# ADE7753.net
KiCad netlist of a schematic drawn in Altium Designer
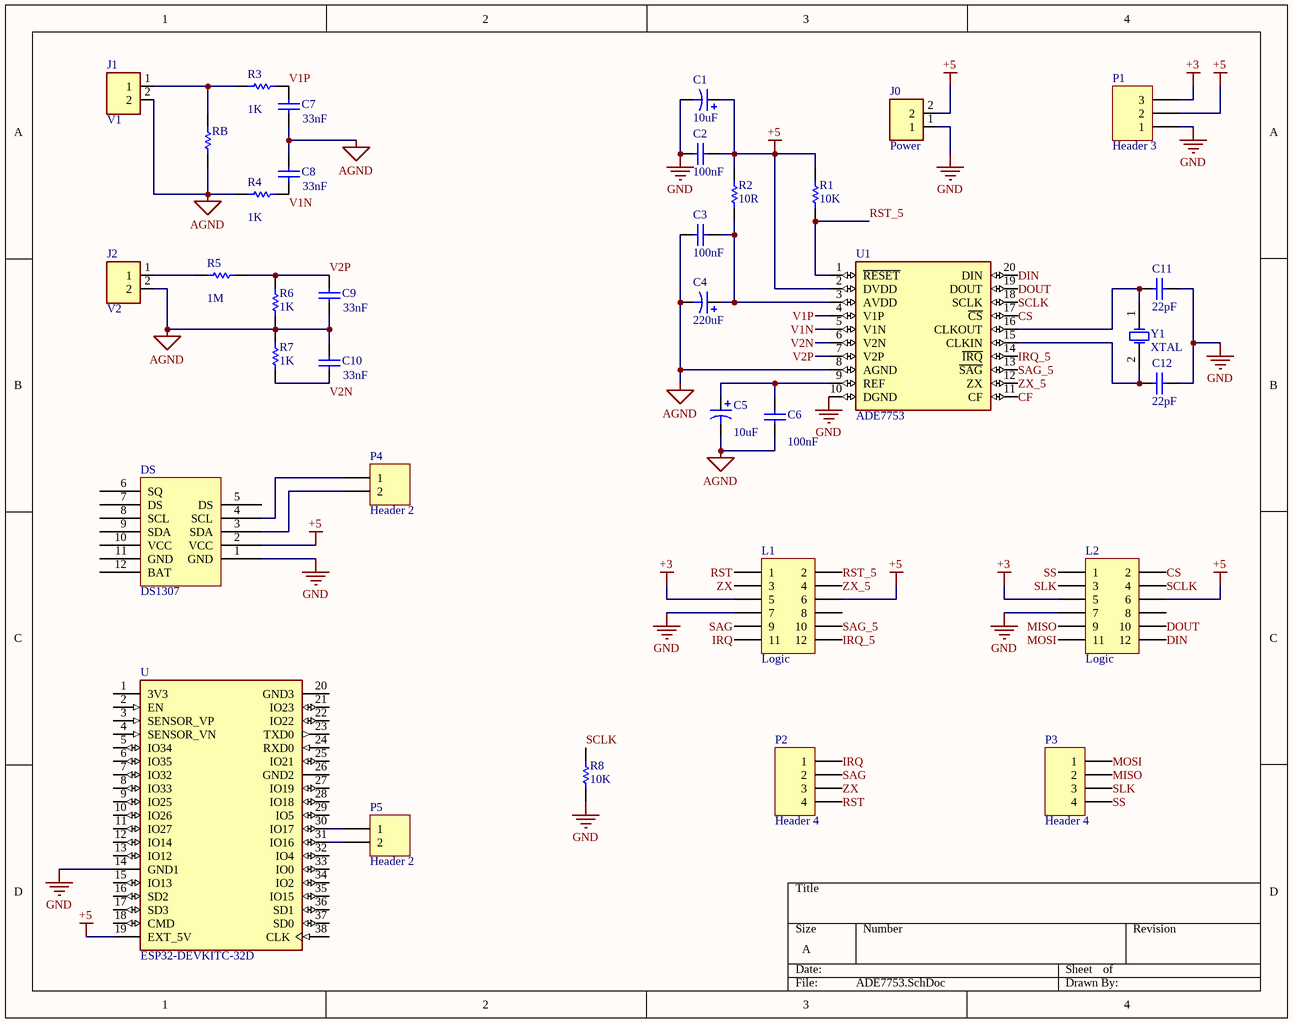
[diagram p0: ADE7753.SchDoc]

(export (version "E")
  (design (tool "Eeschema 10.0.6"))
  (components
    (comp (ref "C1")
      (value "10uF")
      (footprint "Tu hóa 10uF 50v")
      (description "Polarized Capacitor (Radial)")
      (fields (field (name "Comment") "Cap Pol1") (field (name "PUBLISHER") "Altium Limited"))
      (libsource (lib "Miscellaneous Devices") (part "Cap Pol1"))
    )
    (comp (ref "C2")
      (value "100nF")
      (footprint "Tu Gom")
      (description "Capacitor")
      (fields (field (name "Comment") "Cap") (field (name "PUBLISHER") "Altium Limited"))
      (libsource (lib "Miscellaneous Devices") (part "Cap"))
    )
    (comp (ref "C3")
      (value "100nF")
      (footprint "Tu Gom")
      (description "Capacitor")
      (fields (field (name "Comment") "Cap") (field (name "PUBLISHER") "Altium Limited"))
      (libsource (lib "Miscellaneous Devices") (part "Cap"))
    )
    (comp (ref "C4")
      (value "220uF")
      (footprint "Tu hóa 10uF 50v")
      (description "Polarized Capacitor (Radial)")
      (fields (field (name "Comment") "Cap Pol1") (field (name "PUBLISHER") "Altium Limited"))
      (libsource (lib "Miscellaneous Devices") (part "Cap Pol1"))
    )
    (comp (ref "C5")
      (value "10uF")
      (footprint "Tu hóa 10uF 50v")
      (description "Polarized Capacitor (Radial)")
      (fields (field (name "Comment") "Cap Pol1") (field (name "PUBLISHER") "Altium Limited"))
      (libsource (lib "Miscellaneous Devices") (part "Cap Pol1"))
    )
    (comp (ref "C6")
      (value "100nF")
      (footprint "Tu Gom")
      (description "Capacitor")
      (fields (field (name "Comment") "Cap") (field (name "PUBLISHER") "Altium Limited"))
      (libsource (lib "Miscellaneous Devices") (part "Cap"))
    )
    (comp (ref "C7")
      (value "33nF")
      (footprint "Tu Gom")
      (description "Capacitor")
      (fields (field (name "Comment") "Cap") (field (name "PUBLISHER") "Altium Limited"))
      (libsource (lib "Miscellaneous Devices") (part "Cap"))
    )
    (comp (ref "C8")
      (value "33nF")
      (footprint "Tu Gom")
      (description "Capacitor")
      (fields (field (name "Comment") "Cap") (field (name "PUBLISHER") "Altium Limited"))
      (libsource (lib "Miscellaneous Devices") (part "Cap"))
    )
    (comp (ref "C9")
      (value "33nF")
      (footprint "Tu Gom")
      (description "Capacitor")
      (fields (field (name "Comment") "Cap") (field (name "PUBLISHER") "Altium Limited"))
      (libsource (lib "Miscellaneous Devices") (part "Cap"))
    )
    (comp (ref "C10")
      (value "33nF")
      (footprint "Tu Gom")
      (description "Capacitor")
      (fields (field (name "Comment") "Cap") (field (name "PUBLISHER") "Altium Limited"))
      (libsource (lib "Miscellaneous Devices") (part "Cap"))
    )
    (comp (ref "C11")
      (value "22pF")
      (footprint "Tu Gom")
      (description "Capacitor")
      (fields (field (name "Comment") "Cap") (field (name "PUBLISHER") "Altium Limited"))
      (libsource (lib "Miscellaneous Devices") (part "Cap"))
    )
    (comp (ref "C12")
      (value "22pF")
      (footprint "Tu Gom")
      (description "Capacitor")
      (fields (field (name "Comment") "Cap") (field (name "PUBLISHER") "Altium Limited"))
      (libsource (lib "Miscellaneous Devices") (part "Cap"))
    )
    (comp (ref "DS")
      (value "DS1307")
      (footprint "PCBComponent_1")
      (libsource (lib "DS1307") (part "Component_1"))
    )
    (comp (ref "J0")
      (value "Power")
      (footprint "CONN_282836-2")
      (description "TERM BLOCK 2POS SIDE ENTRY 5MM")
      (fields (field (name "MF") "{'manufacturer': u'TE Connectivity'}") (field (name "MP") "282836-2"))
      (libsource (lib "") (part "282836-2_1"))
    )
    (comp (ref "J1")
      (value "V1")
      (footprint "CONN_282836-2")
      (description "TERM BLOCK 2POS SIDE ENTRY 5MM")
      (fields (field (name "MF") "{'manufacturer': u'TE Connectivity'}") (field (name "MP") "282836-2"))
      (libsource (lib "SnapEDA_Library") (part "282836-2"))
    )
    (comp (ref "J2")
      (value "V2")
      (footprint "CONN_282836-2")
      (description "TERM BLOCK 2POS SIDE ENTRY 5MM")
      (fields (field (name "MF") "{'manufacturer': u'TE Connectivity'}") (field (name "MP") "282836-2"))
      (libsource (lib "SnapEDA_Library") (part "282836-2"))
    )
    (comp (ref "L1")
      (value "Logic")
      (footprint "Logic level 3-5")
      (description "Header, 6-Pin, Dual row")
      (fields (field (name "PUBLISHER") "Altium Limited"))
      (libsource (lib "Miscellaneous Connectors") (part "Header 6X2"))
    )
    (comp (ref "L2")
      (value "Logic")
      (footprint "Logic level 3-5")
      (description "Header, 6-Pin, Dual row")
      (fields (field (name "PUBLISHER") "Altium Limited"))
      (libsource (lib "Miscellaneous Connectors") (part "Header 6X2"))
    )
    (comp (ref "P1")
      (value "Header 3")
      (footprint "HDR1X3")
      (description "Header, 3-Pin")
      (fields (field (name "PUBLISHER") "Altium Limited"))
      (libsource (lib "Miscellaneous Connectors") (part "Header 3"))
    )
    (comp (ref "P2")
      (value "Header 4")
      (footprint "HDR1X4")
      (description "Header, 4-Pin")
      (fields (field (name "PUBLISHER") "Altium Limited"))
      (libsource (lib "Miscellaneous Connectors") (part "Header 4"))
    )
    (comp (ref "P3")
      (value "Header 4")
      (footprint "HDR1X4")
      (description "Header, 4-Pin")
      (fields (field (name "PUBLISHER") "Altium Limited"))
      (libsource (lib "Miscellaneous Connectors") (part "Header 4"))
    )
    (comp (ref "P4")
      (value "Header 2")
      (footprint "HDR1X2")
      (description "Header, 2-Pin")
      (fields (field (name "PUBLISHER") "Altium Limited"))
      (libsource (lib "Miscellaneous Connectors") (part "Header 2"))
    )
    (comp (ref "P5")
      (value "Header 2")
      (footprint "HDR1X2")
      (description "Header, 2-Pin")
      (fields (field (name "PUBLISHER") "Altium Limited"))
      (libsource (lib "Miscellaneous Connectors") (part "Header 2"))
    )
    (comp (ref "R1")
      (value "10K")
      (footprint "AXIAL-0.3")
      (description "Resistor")
      (fields (field (name "Comment") "Res1") (field (name "PUBLISHER") "Altium Limited"))
      (libsource (lib "Miscellaneous Devices") (part "Res1"))
    )
    (comp (ref "R2")
      (value "10R")
      (footprint "AXIAL-0.3")
      (description "Resistor")
      (fields (field (name "Comment") "Res1") (field (name "PUBLISHER") "Altium Limited"))
      (libsource (lib "Miscellaneous Devices") (part "Res1"))
    )
    (comp (ref "R3")
      (value "1K")
      (footprint "AXIAL-0.3")
      (description "Resistor")
      (fields (field (name "Comment") "Res1") (field (name "PUBLISHER") "Altium Limited"))
      (libsource (lib "Miscellaneous Devices") (part "Res1"))
    )
    (comp (ref "R4")
      (value "1K")
      (footprint "AXIAL-0.3")
      (description "Resistor")
      (fields (field (name "Comment") "Res1") (field (name "PUBLISHER") "Altium Limited"))
      (libsource (lib "Miscellaneous Devices") (part "Res1"))
    )
    (comp (ref "R5")
      (value "1M")
      (footprint "AXIAL-0.3")
      (description "Resistor")
      (fields (field (name "Comment") "Res1") (field (name "PUBLISHER") "Altium Limited"))
      (libsource (lib "Miscellaneous Devices") (part "Res1"))
    )
    (comp (ref "R6")
      (value "1K")
      (footprint "AXIAL-0.3")
      (description "Resistor")
      (fields (field (name "Comment") "Res1") (field (name "PUBLISHER") "Altium Limited"))
      (libsource (lib "Miscellaneous Devices") (part "Res1"))
    )
    (comp (ref "R7")
      (value "1K")
      (footprint "AXIAL-0.3")
      (description "Resistor")
      (fields (field (name "Comment") "Res1") (field (name "PUBLISHER") "Altium Limited"))
      (libsource (lib "Miscellaneous Devices") (part "Res1"))
    )
    (comp (ref "R8")
      (value "10K")
      (footprint "AXIAL-0.3")
      (description "Resistor")
      (fields (field (name "Comment") "Res1") (field (name "PUBLISHER") "Altium Limited"))
      (libsource (lib "Miscellaneous Devices") (part "Res1"))
    )
    (comp (ref "RB")
      (value "Res1")
      (footprint "AXIAL-0.3")
      (description "Resistor")
      (fields (field (name "PUBLISHER") "Altium Limited"))
      (libsource (lib "Miscellaneous Devices") (part "Res1"))
    )
    (comp (ref "U")
      (value "ESP32-DEVKITC-32D")
      (footprint "MODULE_ESP32-DEVKITC-32D")
      (fields (field (name "MF") "Espressif Systems"))
      (libsource (lib "ESP32-DEVKITC-32D") (part "ESP32-DEVKITC-32D"))
    )
    (comp (ref "U1")
      (value "ADE7753")
      (footprint "ADE_Header")
      (description "Single-Phase Multifunction Metering IC")
      (fields (field (name "MF") "{'manufacturer': u'Analog Devices'}"))
      (libsource (lib "SnapEDA_Library") (part "ADE7753"))
    )
    (comp (ref "Y1")
      (value "XTAL")
      (footprint "3.5795 mhz crystal")
      (description "Crystal Oscillator")
      (fields (field (name "PUBLISHER") "Altium Limited"))
      (libsource (lib "Miscellaneous Devices") (part "XTAL"))
    )
  )
  (nets
    (net (code "1") (name "+3") (class "Default")
      (node (ref "L1") (pin "5") (pinfunction "5_5") (pintype "passive"))
      (node (ref "L2") (pin "5") (pinfunction "5_5") (pintype "passive"))
      (node (ref "P1") (pin "3") (pinfunction "3_3") (pintype "passive"))
    )
    (net (code "2") (name "+5") (class "Default")
      (node (ref "C1") (pin "1") (pinfunction "1_1") (pintype "passive"))
      (node (ref "C2") (pin "1") (pinfunction "1_1") (pintype "passive"))
      (node (ref "DS") (pin "2") (pinfunction "VCC_2") (pintype "passive"))
      (node (ref "J0") (pin "2") (pinfunction "2_2") (pintype "passive"))
      (node (ref "L1") (pin "6") (pinfunction "6_6") (pintype "passive"))
      (node (ref "L2") (pin "6") (pinfunction "6_6") (pintype "passive"))
      (node (ref "P1") (pin "2") (pinfunction "2_2") (pintype "passive"))
      (node (ref "R1") (pin "2") (pinfunction "2_2") (pintype "passive"))
      (node (ref "R2") (pin "2") (pinfunction "2_2") (pintype "passive"))
      (node (ref "U") (pin "19") (pinfunction "EXT_5V_19") (pintype "power_in"))
      (node (ref "U1") (pin "2") (pinfunction "DVDD_2") (pintype "bidirectional"))
    )
    (net (code "3") (name "/CF") (class "Default")
      (node (ref "U1") (pin "11") (pinfunction "CF_11") (pintype "bidirectional"))
    )
    (net (code "4") (name "/CS") (class "Default")
      (node (ref "L2") (pin "2") (pinfunction "2_2") (pintype "passive"))
      (node (ref "U1") (pin "17") (pinfunction "~{CS}_17") (pintype "bidirectional"))
    )
    (net (code "5") (name "/DIN") (class "Default")
      (node (ref "L2") (pin "12") (pinfunction "12_12") (pintype "passive"))
      (node (ref "U1") (pin "20") (pinfunction "DIN_20") (pintype "bidirectional"))
    )
    (net (code "6") (name "/DOUT") (class "Default")
      (node (ref "L2") (pin "10") (pinfunction "10_10") (pintype "passive"))
      (node (ref "U1") (pin "19") (pinfunction "DOUT_19") (pintype "bidirectional"))
    )
    (net (code "7") (name "/IRQ") (class "Default")
      (node (ref "L1") (pin "11") (pinfunction "11_11") (pintype "passive"))
      (node (ref "P2") (pin "1") (pinfunction "1_1") (pintype "passive"))
    )
    (net (code "8") (name "/IRQ_5") (class "Default")
      (node (ref "L1") (pin "12") (pinfunction "12_12") (pintype "passive"))
      (node (ref "U1") (pin "14") (pinfunction "~{IRQ}_14") (pintype "bidirectional"))
    )
    (net (code "9") (name "/MISO") (class "Default")
      (node (ref "L2") (pin "9") (pinfunction "9_9") (pintype "passive"))
      (node (ref "P3") (pin "2") (pinfunction "2_2") (pintype "passive"))
    )
    (net (code "10") (name "/MOSI") (class "Default")
      (node (ref "L2") (pin "11") (pinfunction "11_11") (pintype "passive"))
      (node (ref "P3") (pin "1") (pinfunction "1_1") (pintype "passive"))
    )
    (net (code "11") (name "/RST") (class "Default")
      (node (ref "L1") (pin "1") (pinfunction "1_1") (pintype "passive"))
      (node (ref "P2") (pin "4") (pinfunction "4_4") (pintype "passive"))
    )
    (net (code "12") (name "/RST_5") (class "Default")
      (node (ref "L1") (pin "2") (pinfunction "2_2") (pintype "passive"))
      (node (ref "R1") (pin "1") (pinfunction "1_1") (pintype "passive"))
      (node (ref "U1") (pin "1") (pinfunction "~{RESET}_1") (pintype "bidirectional"))
    )
    (net (code "13") (name "/SAG") (class "Default")
      (node (ref "L1") (pin "9") (pinfunction "9_9") (pintype "passive"))
      (node (ref "P2") (pin "2") (pinfunction "2_2") (pintype "passive"))
    )
    (net (code "14") (name "/SAG_5") (class "Default")
      (node (ref "L1") (pin "10") (pinfunction "10_10") (pintype "passive"))
      (node (ref "U1") (pin "13") (pinfunction "~{SAG}_13") (pintype "bidirectional"))
    )
    (net (code "15") (name "/SCLK") (class "Default")
      (node (ref "L2") (pin "4") (pinfunction "4_4") (pintype "passive"))
      (node (ref "R8") (pin "2") (pinfunction "2_2") (pintype "passive"))
      (node (ref "U1") (pin "18") (pinfunction "SCLK_18") (pintype "bidirectional"))
    )
    (net (code "16") (name "/SLK") (class "Default")
      (node (ref "L2") (pin "3") (pinfunction "3_3") (pintype "passive"))
      (node (ref "P3") (pin "3") (pinfunction "3_3") (pintype "passive"))
    )
    (net (code "17") (name "/SS") (class "Default")
      (node (ref "L2") (pin "1") (pinfunction "1_1") (pintype "passive"))
      (node (ref "P3") (pin "4") (pinfunction "4_4") (pintype "passive"))
    )
    (net (code "18") (name "/V1N") (class "Default")
      (node (ref "C8") (pin "1") (pinfunction "1_1") (pintype "passive"))
      (node (ref "R4") (pin "2") (pinfunction "2_2") (pintype "passive"))
      (node (ref "U1") (pin "5") (pinfunction "V1N_5") (pintype "bidirectional"))
    )
    (net (code "19") (name "/V1P") (class "Default")
      (node (ref "C7") (pin "2") (pinfunction "2_2") (pintype "passive"))
      (node (ref "R3") (pin "2") (pinfunction "2_2") (pintype "passive"))
      (node (ref "U1") (pin "4") (pinfunction "V1P_4") (pintype "bidirectional"))
    )
    (net (code "20") (name "/V2N") (class "Default")
      (node (ref "C10") (pin "1") (pinfunction "1_1") (pintype "passive"))
      (node (ref "R7") (pin "1") (pinfunction "1_1") (pintype "passive"))
      (node (ref "U1") (pin "6") (pinfunction "V2N_6") (pintype "bidirectional"))
    )
    (net (code "21") (name "/V2P") (class "Default")
      (node (ref "C9") (pin "2") (pinfunction "2_2") (pintype "passive"))
      (node (ref "R5") (pin "2") (pinfunction "2_2") (pintype "passive"))
      (node (ref "R6") (pin "2") (pinfunction "2_2") (pintype "passive"))
      (node (ref "U1") (pin "7") (pinfunction "V2P_7") (pintype "bidirectional"))
    )
    (net (code "22") (name "/ZX") (class "Default")
      (node (ref "L1") (pin "3") (pinfunction "3_3") (pintype "passive"))
      (node (ref "P2") (pin "3") (pinfunction "3_3") (pintype "passive"))
    )
    (net (code "23") (name "/ZX_5") (class "Default")
      (node (ref "L1") (pin "4") (pinfunction "4_4") (pintype "passive"))
      (node (ref "U1") (pin "12") (pinfunction "ZX_12") (pintype "bidirectional"))
    )
    (net (code "24") (name "AGND") (class "Default")
      (node (ref "C10") (pin "2") (pinfunction "2_2") (pintype "passive"))
      (node (ref "C3") (pin "2") (pinfunction "2_2") (pintype "passive"))
      (node (ref "C4") (pin "2") (pinfunction "2_2") (pintype "passive"))
      (node (ref "C5") (pin "2") (pinfunction "2_2") (pintype "passive"))
      (node (ref "C6") (pin "1") (pinfunction "1_1") (pintype "passive"))
      (node (ref "C7") (pin "1") (pinfunction "1_1") (pintype "passive"))
      (node (ref "C8") (pin "2") (pinfunction "2_2") (pintype "passive"))
      (node (ref "C9") (pin "1") (pinfunction "1_1") (pintype "passive"))
      (node (ref "J1") (pin "2") (pinfunction "2_2") (pintype "passive"))
      (node (ref "J2") (pin "2") (pinfunction "2_2") (pintype "passive"))
      (node (ref "R4") (pin "1") (pinfunction "1_1") (pintype "passive"))
      (node (ref "R6") (pin "1") (pinfunction "1_1") (pintype "passive"))
      (node (ref "R7") (pin "2") (pinfunction "2_2") (pintype "passive"))
      (node (ref "RB") (pin "1") (pinfunction "1_1") (pintype "passive"))
      (node (ref "U1") (pin "8") (pinfunction "AGND_8") (pintype "bidirectional"))
    )
    (net (code "25") (name "GND") (class "Default")
      (node (ref "C1") (pin "2") (pinfunction "2_2") (pintype "passive"))
      (node (ref "C11") (pin "1") (pinfunction "1_1") (pintype "passive"))
      (node (ref "C12") (pin "1") (pinfunction "1_1") (pintype "passive"))
      (node (ref "C2") (pin "2") (pinfunction "2_2") (pintype "passive"))
      (node (ref "DS") (pin "1") (pinfunction "GND_1") (pintype "passive"))
      (node (ref "J0") (pin "1") (pinfunction "1_1") (pintype "passive"))
      (node (ref "L1") (pin "7") (pinfunction "7_7") (pintype "passive"))
      (node (ref "L2") (pin "7") (pinfunction "7_7") (pintype "passive"))
      (node (ref "P1") (pin "1") (pinfunction "1_1") (pintype "passive"))
      (node (ref "R8") (pin "1") (pinfunction "1_1") (pintype "passive"))
      (node (ref "U") (pin "14") (pinfunction "GND1_14") (pintype "power_in"))
      (node (ref "U1") (pin "10") (pinfunction "DGND_10") (pintype "bidirectional"))
    )
    (net (code "26") (name "Net-(DS-SCL-Pad4)") (class "Default")
      (node (ref "DS") (pin "4") (pinfunction "SCL_4") (pintype "passive"))
      (node (ref "P4") (pin "1") (pinfunction "1_1") (pintype "passive"))
    )
    (net (code "27") (name "Net-(DS-SDA-Pad3)") (class "Default")
      (node (ref "DS") (pin "3") (pinfunction "SDA_3") (pintype "passive"))
      (node (ref "P4") (pin "2") (pinfunction "2_2") (pintype "passive"))
    )
    (net (code "28") (name "Net-(J1-Pad1)") (class "Default")
      (node (ref "J1") (pin "1") (pinfunction "1_1") (pintype "passive"))
      (node (ref "R3") (pin "1") (pinfunction "1_1") (pintype "passive"))
      (node (ref "RB") (pin "2") (pinfunction "2_2") (pintype "passive"))
    )
    (net (code "29") (name "Net-(J2-Pad1)") (class "Default")
      (node (ref "J2") (pin "1") (pinfunction "1_1") (pintype "passive"))
      (node (ref "R5") (pin "1") (pinfunction "1_1") (pintype "passive"))
    )
    (net (code "30") (name "Net-(U-IO16)") (class "Default")
      (node (ref "P5") (pin "2") (pinfunction "2_2") (pintype "passive"))
      (node (ref "U") (pin "31") (pinfunction "IO16_31") (pintype "bidirectional"))
    )
    (net (code "31") (name "Net-(U-IO17)") (class "Default")
      (node (ref "P5") (pin "1") (pinfunction "1_1") (pintype "passive"))
      (node (ref "U") (pin "30") (pinfunction "IO17_30") (pintype "bidirectional"))
    )
    (net (code "32") (name "Net-(U1-AVDD)") (class "Default")
      (node (ref "C3") (pin "1") (pinfunction "1_1") (pintype "passive"))
      (node (ref "C4") (pin "1") (pinfunction "1_1") (pintype "passive"))
      (node (ref "R2") (pin "1") (pinfunction "1_1") (pintype "passive"))
      (node (ref "U1") (pin "3") (pinfunction "AVDD_3") (pintype "bidirectional"))
    )
    (net (code "33") (name "Net-(U1-CLKIN)") (class "Default")
      (node (ref "C12") (pin "2") (pinfunction "2_2") (pintype "passive"))
      (node (ref "U1") (pin "15") (pinfunction "CLKIN_15") (pintype "bidirectional"))
      (node (ref "Y1") (pin "2") (pinfunction "OSC2_2") (pintype "passive"))
    )
    (net (code "34") (name "Net-(U1-CLKOUT)") (class "Default")
      (node (ref "C11") (pin "2") (pinfunction "2_2") (pintype "passive"))
      (node (ref "U1") (pin "16") (pinfunction "CLKOUT_16") (pintype "bidirectional"))
      (node (ref "Y1") (pin "1") (pinfunction "OSC1_1") (pintype "passive"))
    )
    (net (code "35") (name "Net-(U1-REF)") (class "Default")
      (node (ref "C5") (pin "1") (pinfunction "1_1") (pintype "passive"))
      (node (ref "C6") (pin "2") (pinfunction "2_2") (pintype "passive"))
      (node (ref "U1") (pin "9") (pinfunction "REF_9") (pintype "bidirectional"))
    )
    (net (code "36") (name "unconnected-(DS-BAT-Pad12)") (class "Default")
      (node (ref "DS") (pin "12") (pinfunction "BAT_12") (pintype "passive"))
    )
    (net (code "37") (name "unconnected-(DS-DS-Pad5)") (class "Default")
      (node (ref "DS") (pin "5") (pinfunction "DS_5") (pintype "passive"))
    )
    (net (code "38") (name "unconnected-(DS-DS-Pad7)") (class "Default")
      (node (ref "DS") (pin "7") (pinfunction "DS_7") (pintype "passive"))
    )
    (net (code "39") (name "unconnected-(DS-GND-Pad11)") (class "Default")
      (node (ref "DS") (pin "11") (pinfunction "GND_11") (pintype "passive"))
    )
    (net (code "40") (name "unconnected-(DS-SCL-Pad8)") (class "Default")
      (node (ref "DS") (pin "8") (pinfunction "SCL_8") (pintype "passive"))
    )
    (net (code "41") (name "unconnected-(DS-SDA-Pad9)") (class "Default")
      (node (ref "DS") (pin "9") (pinfunction "SDA_9") (pintype "passive"))
    )
    (net (code "42") (name "unconnected-(DS-SQ-Pad6)") (class "Default")
      (node (ref "DS") (pin "6") (pinfunction "SQ_6") (pintype "passive"))
    )
    (net (code "43") (name "unconnected-(DS-VCC-Pad10)") (class "Default")
      (node (ref "DS") (pin "10") (pinfunction "VCC_10") (pintype "passive"))
    )
    (net (code "44") (name "unconnected-(L1-Pad8)") (class "Default")
      (node (ref "L1") (pin "8") (pinfunction "8_8") (pintype "passive"))
    )
    (net (code "45") (name "unconnected-(L2-Pad8)") (class "Default")
      (node (ref "L2") (pin "8") (pinfunction "8_8") (pintype "passive"))
    )
    (net (code "46") (name "unconnected-(U-3V3-Pad1)") (class "Default")
      (node (ref "U") (pin "1") (pinfunction "3V3_1") (pintype "power_in"))
    )
    (net (code "47") (name "unconnected-(U-CLK-Pad38)") (class "Default")
      (node (ref "U") (pin "38") (pinfunction "CLK_38") (pintype "input"))
    )
    (net (code "48") (name "unconnected-(U-CMD-Pad18)") (class "Default")
      (node (ref "U") (pin "18") (pinfunction "CMD_18") (pintype "bidirectional"))
    )
    (net (code "49") (name "unconnected-(U-EN-Pad2)") (class "Default")
      (node (ref "U") (pin "2") (pinfunction "EN_2") (pintype "input"))
    )
    (net (code "50") (name "unconnected-(U-GND2-Pad26)") (class "Default")
      (node (ref "U") (pin "26") (pinfunction "GND2_26") (pintype "power_in"))
    )
    (net (code "51") (name "unconnected-(U-GND3-Pad20)") (class "Default")
      (node (ref "U") (pin "20") (pinfunction "GND3_20") (pintype "power_in"))
    )
    (net (code "52") (name "unconnected-(U-IO0-Pad33)") (class "Default")
      (node (ref "U") (pin "33") (pinfunction "IO0_33") (pintype "bidirectional"))
    )
    (net (code "53") (name "unconnected-(U-IO2-Pad34)") (class "Default")
      (node (ref "U") (pin "34") (pinfunction "IO2_34") (pintype "bidirectional"))
    )
    (net (code "54") (name "unconnected-(U-IO4-Pad32)") (class "Default")
      (node (ref "U") (pin "32") (pinfunction "IO4_32") (pintype "bidirectional"))
    )
    (net (code "55") (name "unconnected-(U-IO5-Pad29)") (class "Default")
      (node (ref "U") (pin "29") (pinfunction "IO5_29") (pintype "bidirectional"))
    )
    (net (code "56") (name "unconnected-(U-IO12-Pad13)") (class "Default")
      (node (ref "U") (pin "13") (pinfunction "IO12_13") (pintype "bidirectional"))
    )
    (net (code "57") (name "unconnected-(U-IO13-Pad15)") (class "Default")
      (node (ref "U") (pin "15") (pinfunction "IO13_15") (pintype "bidirectional"))
    )
    (net (code "58") (name "unconnected-(U-IO14-Pad12)") (class "Default")
      (node (ref "U") (pin "12") (pinfunction "IO14_12") (pintype "bidirectional"))
    )
    (net (code "59") (name "unconnected-(U-IO15-Pad35)") (class "Default")
      (node (ref "U") (pin "35") (pinfunction "IO15_35") (pintype "bidirectional"))
    )
    (net (code "60") (name "unconnected-(U-IO18-Pad28)") (class "Default")
      (node (ref "U") (pin "28") (pinfunction "IO18_28") (pintype "bidirectional"))
    )
    (net (code "61") (name "unconnected-(U-IO19-Pad27)") (class "Default")
      (node (ref "U") (pin "27") (pinfunction "IO19_27") (pintype "bidirectional"))
    )
    (net (code "62") (name "unconnected-(U-IO21-Pad25)") (class "Default")
      (node (ref "U") (pin "25") (pinfunction "IO21_25") (pintype "bidirectional"))
    )
    (net (code "63") (name "unconnected-(U-IO22-Pad22)") (class "Default")
      (node (ref "U") (pin "22") (pinfunction "IO22_22") (pintype "bidirectional"))
    )
    (net (code "64") (name "unconnected-(U-IO23-Pad21)") (class "Default")
      (node (ref "U") (pin "21") (pinfunction "IO23_21") (pintype "bidirectional"))
    )
    (net (code "65") (name "unconnected-(U-IO25-Pad9)") (class "Default")
      (node (ref "U") (pin "9") (pinfunction "IO25_9") (pintype "bidirectional"))
    )
    (net (code "66") (name "unconnected-(U-IO26-Pad10)") (class "Default")
      (node (ref "U") (pin "10") (pinfunction "IO26_10") (pintype "bidirectional"))
    )
    (net (code "67") (name "unconnected-(U-IO27-Pad11)") (class "Default")
      (node (ref "U") (pin "11") (pinfunction "IO27_11") (pintype "bidirectional"))
    )
    (net (code "68") (name "unconnected-(U-IO32-Pad7)") (class "Default")
      (node (ref "U") (pin "7") (pinfunction "IO32_7") (pintype "bidirectional"))
    )
    (net (code "69") (name "unconnected-(U-IO33-Pad8)") (class "Default")
      (node (ref "U") (pin "8") (pinfunction "IO33_8") (pintype "bidirectional"))
    )
    (net (code "70") (name "unconnected-(U-IO34-Pad5)") (class "Default")
      (node (ref "U") (pin "5") (pinfunction "IO34_5") (pintype "bidirectional"))
    )
    (net (code "71") (name "unconnected-(U-IO35-Pad6)") (class "Default")
      (node (ref "U") (pin "6") (pinfunction "IO35_6") (pintype "bidirectional"))
    )
    (net (code "72") (name "unconnected-(U-RXD0-Pad24)") (class "Default")
      (node (ref "U") (pin "24") (pinfunction "RXD0_24") (pintype "input"))
    )
    (net (code "73") (name "unconnected-(U-SD0-Pad37)") (class "Default")
      (node (ref "U") (pin "37") (pinfunction "SD0_37") (pintype "bidirectional"))
    )
    (net (code "74") (name "unconnected-(U-SD1-Pad36)") (class "Default")
      (node (ref "U") (pin "36") (pinfunction "SD1_36") (pintype "bidirectional"))
    )
    (net (code "75") (name "unconnected-(U-SD2-Pad16)") (class "Default")
      (node (ref "U") (pin "16") (pinfunction "SD2_16") (pintype "bidirectional"))
    )
    (net (code "76") (name "unconnected-(U-SD3-Pad17)") (class "Default")
      (node (ref "U") (pin "17") (pinfunction "SD3_17") (pintype "bidirectional"))
    )
    (net (code "77") (name "unconnected-(U-SENSOR_VN-Pad4)") (class "Default")
      (node (ref "U") (pin "4") (pinfunction "SENSOR_VN_4") (pintype "input"))
    )
    (net (code "78") (name "unconnected-(U-SENSOR_VP-Pad3)") (class "Default")
      (node (ref "U") (pin "3") (pinfunction "SENSOR_VP_3") (pintype "input"))
    )
    (net (code "79") (name "unconnected-(U-TXD0-Pad23)") (class "Default")
      (node (ref "U") (pin "23") (pinfunction "TXD0_23") (pintype "output"))
    )
  )
)
